# SCH_Wack-a-Mole_2025-09-20.net
KiCad netlist of a schematic drawn in EasyEDA
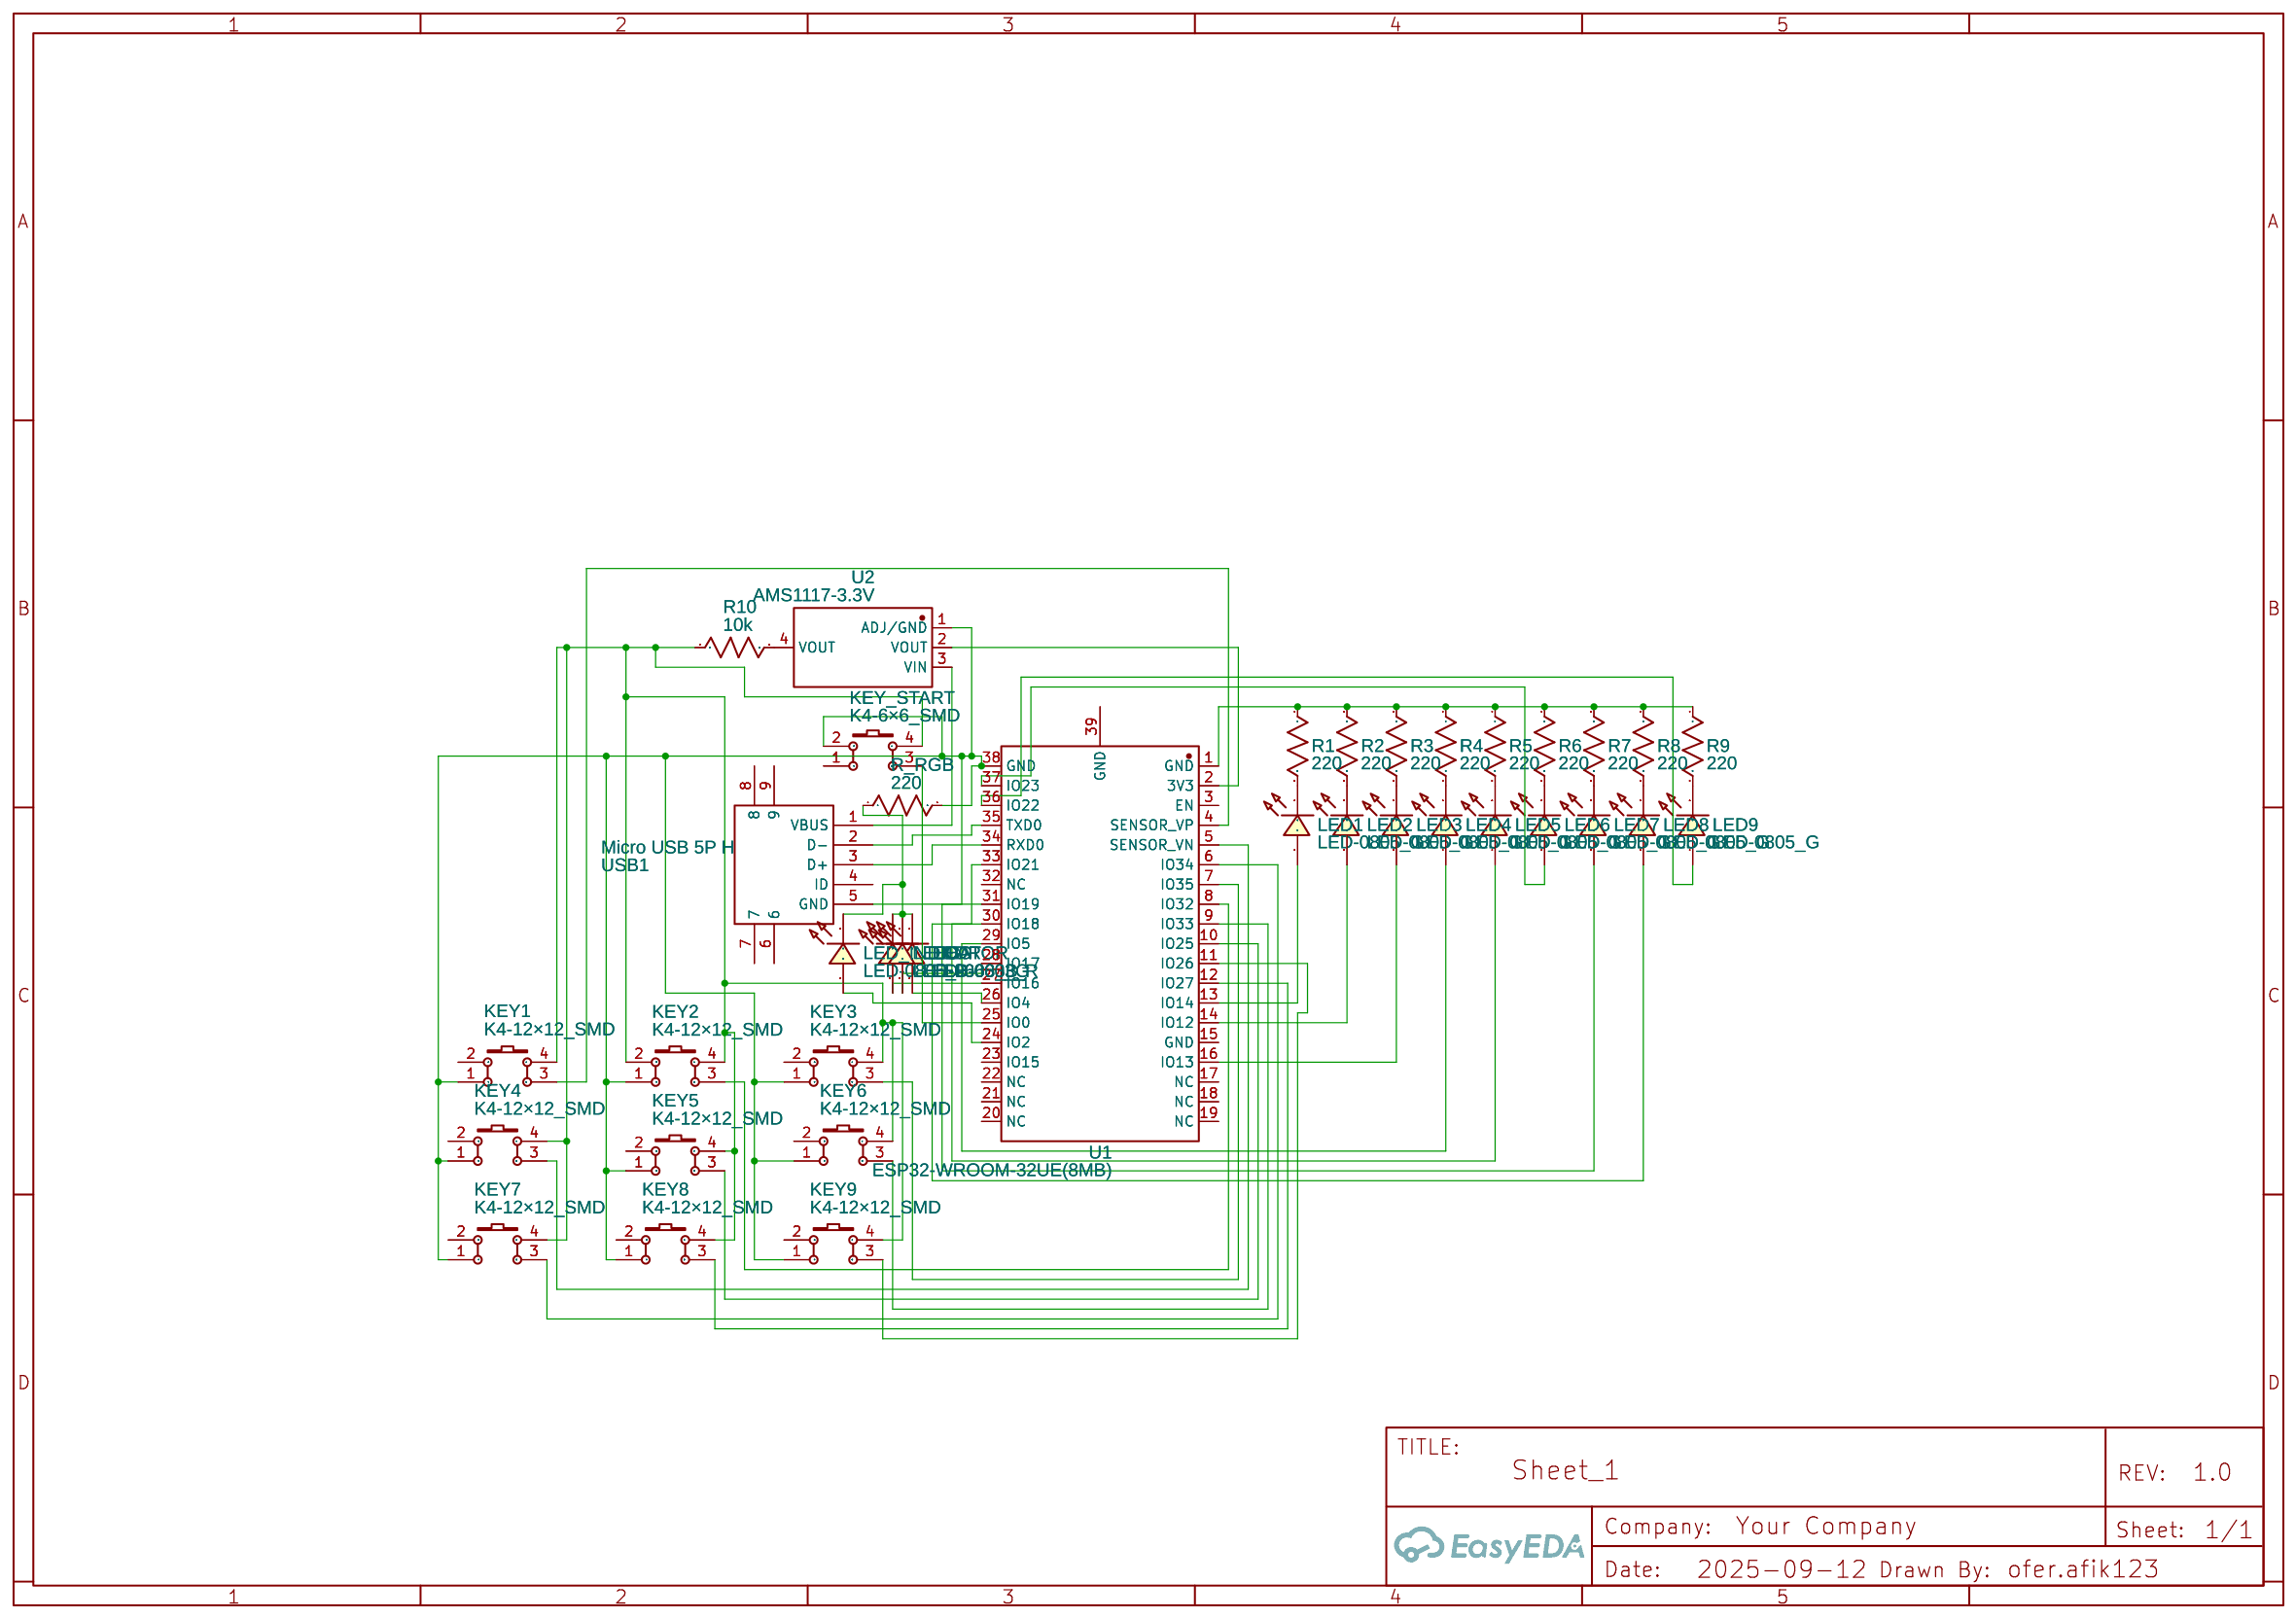
[diagram p0: schematic sheet]

(export (version "E")
  (design (tool "Eeschema 10.0.6"))
  (components
    (comp (ref "KEY1")
      (value "K4-12×12_SMD")
      (fields (field (name "Manufacturer Part") "K2-1103SP-E4SW-04") (field (name "Manufacturer") "韩国韩荣"))
      (libsource (lib "") (part "K4-12×12_SMD"))
    )
    (comp (ref "KEY2")
      (value "K4-12×12_SMD")
      (fields (field (name "Manufacturer Part") "K2-1103SP-E4SW-04") (field (name "Manufacturer") "韩国韩荣"))
      (libsource (lib "") (part "K4-12×12_SMD"))
    )
    (comp (ref "KEY3")
      (value "K4-12×12_SMD")
      (fields (field (name "Manufacturer Part") "K2-1103SP-E4SW-04") (field (name "Manufacturer") "韩国韩荣"))
      (libsource (lib "") (part "K4-12×12_SMD"))
    )
    (comp (ref "KEY4")
      (value "K4-12×12_SMD")
      (fields (field (name "Manufacturer Part") "K2-1103SP-E4SW-04") (field (name "Manufacturer") "韩国韩荣"))
      (libsource (lib "") (part "K4-12×12_SMD"))
    )
    (comp (ref "KEY5")
      (value "K4-12×12_SMD")
      (fields (field (name "Manufacturer Part") "K2-1103SP-E4SW-04") (field (name "Manufacturer") "韩国韩荣"))
      (libsource (lib "") (part "K4-12×12_SMD"))
    )
    (comp (ref "KEY6")
      (value "K4-12×12_SMD")
      (fields (field (name "Manufacturer Part") "K2-1103SP-E4SW-04") (field (name "Manufacturer") "韩国韩荣"))
      (libsource (lib "") (part "K4-12×12_SMD"))
    )
    (comp (ref "KEY7")
      (value "K4-12×12_SMD")
      (fields (field (name "Manufacturer Part") "K2-1103SP-E4SW-04") (field (name "Manufacturer") "韩国韩荣"))
      (libsource (lib "") (part "K4-12×12_SMD"))
    )
    (comp (ref "KEY8")
      (value "K4-12×12_SMD")
      (fields (field (name "Manufacturer Part") "K2-1103SP-E4SW-04") (field (name "Manufacturer") "韩国韩荣"))
      (libsource (lib "") (part "K4-12×12_SMD"))
    )
    (comp (ref "KEY9")
      (value "K4-12×12_SMD")
      (fields (field (name "Manufacturer Part") "K2-1103SP-E4SW-04") (field (name "Manufacturer") "韩国韩荣"))
      (libsource (lib "") (part "K4-12×12_SMD"))
    )
    (comp (ref "KEY_START")
      (value "K4-6×6_SMD")
      (fields (field (name "Manufacturer Part") "K2-6639SP-D4SC-04") (field (name "Manufacturer") "韩国韩荣"))
      (libsource (lib "") (part "K4-6×6_SMD"))
    )
    (comp (ref "LED1")
      (value "LED-0805_G")
      (fields (field (name "Manufacturer Part") "NCD0805G1") (field (name "Manufacturer") "国星光电"))
      (libsource (lib "") (part "LED-0805_G"))
    )
    (comp (ref "LED2")
      (value "LED-0805_G")
      (fields (field (name "Manufacturer Part") "NCD0805G1") (field (name "Manufacturer") "国星光电"))
      (libsource (lib "") (part "LED-0805_G"))
    )
    (comp (ref "LED3")
      (value "LED-0805_G")
      (fields (field (name "Manufacturer Part") "NCD0805G1") (field (name "Manufacturer") "国星光电"))
      (libsource (lib "") (part "LED-0805_G"))
    )
    (comp (ref "LED4")
      (value "LED-0805_G")
      (fields (field (name "Manufacturer Part") "NCD0805G1") (field (name "Manufacturer") "国星光电"))
      (libsource (lib "") (part "LED-0805_G"))
    )
    (comp (ref "LED5")
      (value "LED-0805_G")
      (fields (field (name "Manufacturer Part") "NCD0805G1") (field (name "Manufacturer") "国星光电"))
      (libsource (lib "") (part "LED-0805_G"))
    )
    (comp (ref "LED6")
      (value "LED-0805_G")
      (fields (field (name "Manufacturer Part") "NCD0805G1") (field (name "Manufacturer") "国星光电"))
      (libsource (lib "") (part "LED-0805_G"))
    )
    (comp (ref "LED7")
      (value "LED-0805_G")
      (fields (field (name "Manufacturer Part") "NCD0805G1") (field (name "Manufacturer") "国星光电"))
      (libsource (lib "") (part "LED-0805_G"))
    )
    (comp (ref "LED8")
      (value "LED-0805_G")
      (fields (field (name "Manufacturer Part") "NCD0805G1") (field (name "Manufacturer") "国星光电"))
      (libsource (lib "") (part "LED-0805_G"))
    )
    (comp (ref "LED9")
      (value "LED-0805_G")
      (fields (field (name "Manufacturer Part") "NCD0805G1") (field (name "Manufacturer") "国星光电"))
      (libsource (lib "") (part "LED-0805_G"))
    )
    (comp (ref "LEDB")
      (value "LED-0603_B")
      (fields
        (field (name "Manufacturer Part") "19-217/BHC-ZL1M2RY/3T")
        (field (name "Manufacturer") "EVERLIGHT(台湾亿光)")
      )
      (libsource (lib "") (part "LED-0603_B"))
    )
    (comp (ref "LEDG")
      (value "LED-0603_G")
      (fields
        (field (name "Manufacturer Part") "19-217/GHC-YR1S2/3T")
        (field (name "Manufacturer") "EVERLIGHT(台湾亿光)")
      )
      (libsource (lib "") (part "LED-0603_G"))
    )
    (comp (ref "LEDR")
      (value "LED-0603_R")
      (fields
        (field (name "Manufacturer Part") "19-217/R6C-AL1M2VY/3T")
        (field (name "Manufacturer") "EVERLIGHT(台湾亿光)")
      )
      (libsource (lib "") (part "LED-0603_R"))
    )
    (comp (ref "LED_INDICATOR")
      (value "LED-0805_B")
      (fields (field (name "Manufacturer Part") "D-B080508B1-KS2") (field (name "Manufacturer") "方舟 ARKLED"))
      (libsource (lib "") (part "LED-0805_B"))
    )
    (comp (ref "R1") (value "220") (libsource (lib "") (part "R_0402_US")))
    (comp (ref "R2") (value "220") (libsource (lib "") (part "R_0402_US")))
    (comp (ref "R3") (value "220") (libsource (lib "") (part "R_0402_US")))
    (comp (ref "R4") (value "220") (libsource (lib "") (part "R_0402_US")))
    (comp (ref "R5") (value "220") (libsource (lib "") (part "R_0402_US")))
    (comp (ref "R6") (value "220") (libsource (lib "") (part "R_0402_US")))
    (comp (ref "R7") (value "220") (libsource (lib "") (part "R_0402_US")))
    (comp (ref "R8") (value "220") (libsource (lib "") (part "R_0402_US")))
    (comp (ref "R9") (value "220") (libsource (lib "") (part "R_0402_US")))
    (comp (ref "R10") (value "10k") (libsource (lib "") (part "R_0402_US_1")))
    (comp (ref "R_RGB") (value "220") (libsource (lib "") (part "R_0201_US")))
    (comp (ref "U1")
      (value "ESP32-WROOM-32UE(8MB)")
      (fields
        (field (name "Manufacturer Part") "ESP32-WROOM-32UE-N8")
        (field (name "Manufacturer") "ESPRESSIF(乐鑫)")
      )
      (libsource (lib "") (part "ESP32-WROOM-32UE(8MB)"))
    )
    (comp (ref "U2")
      (value "AMS1117-3.3V")
      (fields (field (name "Manufacturer") "WPMtek(维攀)"))
      (libsource (lib "") (part "AMS1117-3.3V"))
    )
    (comp (ref "USB1")
      (value "Micro USB 5P H")
      (fields (field (name "Manufacturer Part") "920-E52A2021S10101") (field (name "Manufacturer") "精拓金"))
      (libsource (lib "") (part "Micro USB 5P H"))
    )
  )
  (nets
    (net (code "1") (name "Net-(KEY1-Pad4)") (class "Default")
      (node (ref "KEY1") (pin "4") (pinfunction "4_4") (pintype "unspecified"))
      (node (ref "KEY2") (pin "2") (pinfunction "2_2") (pintype "unspecified"))
      (node (ref "KEY2") (pin "4") (pinfunction "4_4") (pintype "unspecified"))
      (node (ref "KEY3") (pin "4") (pinfunction "4_4") (pintype "unspecified"))
      (node (ref "KEY4") (pin "4") (pinfunction "4_4") (pintype "unspecified"))
      (node (ref "KEY5") (pin "4") (pinfunction "4_4") (pintype "unspecified"))
      (node (ref "KEY6") (pin "4") (pinfunction "4_4") (pintype "unspecified"))
      (node (ref "KEY7") (pin "4") (pinfunction "4_4") (pintype "unspecified"))
      (node (ref "KEY8") (pin "4") (pinfunction "4_4") (pintype "unspecified"))
      (node (ref "KEY9") (pin "4") (pinfunction "4_4") (pintype "unspecified"))
      (node (ref "KEY_START") (pin "4") (pinfunction "4_4") (pintype "unspecified"))
      (node (ref "R10") (pin "1") (pinfunction "1_1") (pintype "unspecified"))
    )
    (net (code "2") (name "Net-(LED1-Pad2)") (class "Default")
      (node (ref "LED1") (pin "2") (pinfunction "2_2") (pintype "unspecified"))
      (node (ref "R1") (pin "2") (pinfunction "2_2") (pintype "unspecified"))
    )
    (net (code "3") (name "Net-(LED2-Pad2)") (class "Default")
      (node (ref "LED2") (pin "2") (pinfunction "2_2") (pintype "unspecified"))
      (node (ref "R2") (pin "2") (pinfunction "2_2") (pintype "unspecified"))
    )
    (net (code "4") (name "Net-(LED3-Pad2)") (class "Default")
      (node (ref "LED3") (pin "2") (pinfunction "2_2") (pintype "unspecified"))
      (node (ref "R3") (pin "2") (pinfunction "2_2") (pintype "unspecified"))
    )
    (net (code "5") (name "Net-(LED4-Pad2)") (class "Default")
      (node (ref "LED4") (pin "2") (pinfunction "2_2") (pintype "unspecified"))
      (node (ref "R4") (pin "2") (pinfunction "2_2") (pintype "unspecified"))
    )
    (net (code "6") (name "Net-(LED5-Pad2)") (class "Default")
      (node (ref "LED5") (pin "2") (pinfunction "2_2") (pintype "unspecified"))
      (node (ref "R5") (pin "2") (pinfunction "2_2") (pintype "unspecified"))
    )
    (net (code "7") (name "Net-(LED6-Pad2)") (class "Default")
      (node (ref "LED6") (pin "2") (pinfunction "2_2") (pintype "unspecified"))
      (node (ref "R6") (pin "2") (pinfunction "2_2") (pintype "unspecified"))
    )
    (net (code "8") (name "Net-(LED7-Pad2)") (class "Default")
      (node (ref "LED7") (pin "2") (pinfunction "2_2") (pintype "unspecified"))
      (node (ref "R7") (pin "2") (pinfunction "2_2") (pintype "unspecified"))
    )
    (net (code "9") (name "Net-(LED8-Pad2)") (class "Default")
      (node (ref "LED8") (pin "2") (pinfunction "2_2") (pintype "unspecified"))
      (node (ref "R8") (pin "2") (pinfunction "2_2") (pintype "unspecified"))
    )
    (net (code "10") (name "Net-(LED9-Pad2)") (class "Default")
      (node (ref "LED9") (pin "2") (pinfunction "2_2") (pintype "unspecified"))
      (node (ref "R9") (pin "2") (pinfunction "2_2") (pintype "unspecified"))
    )
    (net (code "11") (name "Net-(LEDB-Pad2)") (class "Default")
      (node (ref "LEDB") (pin "2") (pinfunction "2_2") (pintype "unspecified"))
      (node (ref "LEDG") (pin "2") (pinfunction "2_2") (pintype "unspecified"))
      (node (ref "LEDR") (pin "2") (pinfunction "2_2") (pintype "unspecified"))
      (node (ref "LED_INDICATOR") (pin "2") (pinfunction "2_2") (pintype "unspecified"))
      (node (ref "R_RGB") (pin "1") (pinfunction "1_1") (pintype "unspecified"))
    )
    (net (code "12") (name "Net-(R1-Pad1)") (class "Default")
      (node (ref "R1") (pin "1") (pinfunction "1_1") (pintype "unspecified"))
      (node (ref "R2") (pin "1") (pinfunction "1_1") (pintype "unspecified"))
      (node (ref "R3") (pin "1") (pinfunction "1_1") (pintype "unspecified"))
      (node (ref "R4") (pin "1") (pinfunction "1_1") (pintype "unspecified"))
      (node (ref "R5") (pin "1") (pinfunction "1_1") (pintype "unspecified"))
      (node (ref "R6") (pin "1") (pinfunction "1_1") (pintype "unspecified"))
      (node (ref "R7") (pin "1") (pinfunction "1_1") (pintype "unspecified"))
      (node (ref "R8") (pin "1") (pinfunction "1_1") (pintype "unspecified"))
      (node (ref "R9") (pin "1") (pinfunction "1_1") (pintype "unspecified"))
      (node (ref "U1") (pin "1") (pinfunction "GND_1") (pintype "unspecified"))
    )
    (net (code "13") (name "Net-(R10-Pad2)") (class "Default")
      (node (ref "R10") (pin "2") (pinfunction "2_2") (pintype "unspecified"))
      (node (ref "U2") (pin "4") (pinfunction "VOUT_4") (pintype "unspecified"))
    )
    (net (code "14") (name "Net-(U1-3V3)") (class "Default")
      (node (ref "U1") (pin "2") (pinfunction "3V3_2") (pintype "unspecified"))
      (node (ref "U2") (pin "2") (pinfunction "VOUT_2") (pintype "unspecified"))
    )
    (net (code "15") (name "Net-(U1-IO0)") (class "Default")
      (node (ref "KEY_START") (pin "3") (pinfunction "3_3") (pintype "unspecified"))
      (node (ref "U1") (pin "25") (pinfunction "IO0_25") (pintype "unspecified"))
    )
    (net (code "16") (name "Net-(U1-IO2)") (class "Default")
      (node (ref "LED_INDICATOR") (pin "1") (pinfunction "1_1") (pintype "unspecified"))
      (node (ref "U1") (pin "24") (pinfunction "IO2_24") (pintype "unspecified"))
    )
    (net (code "17") (name "Net-(U1-IO4)") (class "Default")
      (node (ref "LEDR") (pin "1") (pinfunction "1_1") (pintype "unspecified"))
      (node (ref "U1") (pin "26") (pinfunction "IO4_26") (pintype "unspecified"))
    )
    (net (code "18") (name "Net-(U1-IO5)") (class "Default")
      (node (ref "LED4") (pin "1") (pinfunction "1_1") (pintype "unspecified"))
      (node (ref "U1") (pin "29") (pinfunction "IO5_29") (pintype "unspecified"))
    )
    (net (code "19") (name "Net-(U1-IO12)") (class "Default")
      (node (ref "LED2") (pin "1") (pinfunction "1_1") (pintype "unspecified"))
      (node (ref "U1") (pin "14") (pinfunction "IO12_14") (pintype "unspecified"))
    )
    (net (code "20") (name "Net-(U1-IO13)") (class "Default")
      (node (ref "LED3") (pin "1") (pinfunction "1_1") (pintype "unspecified"))
      (node (ref "U1") (pin "16") (pinfunction "IO13_16") (pintype "unspecified"))
    )
    (net (code "21") (name "Net-(U1-IO14)") (class "Default")
      (node (ref "LED1") (pin "1") (pinfunction "1_1") (pintype "unspecified"))
      (node (ref "U1") (pin "13") (pinfunction "IO14_13") (pintype "unspecified"))
    )
    (net (code "22") (name "Net-(U1-IO16)") (class "Default")
      (node (ref "LEDB") (pin "1") (pinfunction "1_1") (pintype "unspecified"))
      (node (ref "U1") (pin "27") (pinfunction "IO16_27") (pintype "unspecified"))
    )
    (net (code "23") (name "Net-(U1-IO17)") (class "Default")
      (node (ref "LEDG") (pin "1") (pinfunction "1_1") (pintype "unspecified"))
      (node (ref "U1") (pin "28") (pinfunction "IO17_28") (pintype "unspecified"))
    )
    (net (code "24") (name "Net-(U1-IO18)") (class "Default")
      (node (ref "LED8") (pin "1") (pinfunction "1_1") (pintype "unspecified"))
      (node (ref "U1") (pin "30") (pinfunction "IO18_30") (pintype "unspecified"))
    )
    (net (code "25") (name "Net-(U1-IO19)") (class "Default")
      (node (ref "LED7") (pin "1") (pinfunction "1_1") (pintype "unspecified"))
      (node (ref "U1") (pin "31") (pinfunction "IO19_31") (pintype "unspecified"))
    )
    (net (code "26") (name "Net-(U1-IO21)") (class "Default")
      (node (ref "LED5") (pin "1") (pinfunction "1_1") (pintype "unspecified"))
      (node (ref "U1") (pin "33") (pinfunction "IO21_33") (pintype "unspecified"))
    )
    (net (code "27") (name "Net-(U1-IO22)") (class "Default")
      (node (ref "LED9") (pin "1") (pinfunction "1_1") (pintype "unspecified"))
      (node (ref "U1") (pin "36") (pinfunction "IO22_36") (pintype "unspecified"))
    )
    (net (code "28") (name "Net-(U1-IO23)") (class "Default")
      (node (ref "LED6") (pin "1") (pinfunction "1_1") (pintype "unspecified"))
      (node (ref "U1") (pin "37") (pinfunction "IO23_37") (pintype "unspecified"))
    )
    (net (code "29") (name "Net-(U1-IO25)") (class "Default")
      (node (ref "KEY5") (pin "3") (pinfunction "3_3") (pintype "unspecified"))
      (node (ref "U1") (pin "10") (pinfunction "IO25_10") (pintype "unspecified"))
    )
    (net (code "30") (name "Net-(U1-IO26)") (class "Default")
      (node (ref "KEY9") (pin "3") (pinfunction "3_3") (pintype "unspecified"))
      (node (ref "U1") (pin "11") (pinfunction "IO26_11") (pintype "unspecified"))
    )
    (net (code "31") (name "Net-(U1-IO27)") (class "Default")
      (node (ref "KEY8") (pin "3") (pinfunction "3_3") (pintype "unspecified"))
      (node (ref "U1") (pin "12") (pinfunction "IO27_12") (pintype "unspecified"))
    )
    (net (code "32") (name "Net-(U1-IO32)") (class "Default")
      (node (ref "KEY2") (pin "3") (pinfunction "3_3") (pintype "unspecified"))
      (node (ref "U1") (pin "8") (pinfunction "IO32_8") (pintype "unspecified"))
    )
    (net (code "33") (name "Net-(U1-IO33)") (class "Default")
      (node (ref "KEY6") (pin "3") (pinfunction "3_3") (pintype "unspecified"))
      (node (ref "U1") (pin "9") (pinfunction "IO33_9") (pintype "unspecified"))
    )
    (net (code "34") (name "Net-(U1-IO34)") (class "Default")
      (node (ref "KEY7") (pin "3") (pinfunction "3_3") (pintype "unspecified"))
      (node (ref "U1") (pin "6") (pinfunction "IO34_6") (pintype "unspecified"))
    )
    (net (code "35") (name "Net-(U1-IO35)") (class "Default")
      (node (ref "KEY3") (pin "3") (pinfunction "3_3") (pintype "unspecified"))
      (node (ref "U1") (pin "7") (pinfunction "IO35_7") (pintype "unspecified"))
    )
    (net (code "36") (name "Net-(U1-RXD0)") (class "Default")
      (node (ref "U1") (pin "34") (pinfunction "RXD0_34") (pintype "unspecified"))
      (node (ref "USB1") (pin "3") (pinfunction "D+_3") (pintype "unspecified"))
    )
    (net (code "37") (name "Net-(U1-SENSOR_VN)") (class "Default")
      (node (ref "KEY4") (pin "3") (pinfunction "3_3") (pintype "unspecified"))
      (node (ref "U1") (pin "5") (pinfunction "SENSOR_VN_5") (pintype "unspecified"))
    )
    (net (code "38") (name "Net-(U1-SENSOR_VP)") (class "Default")
      (node (ref "KEY1") (pin "3") (pinfunction "3_3") (pintype "unspecified"))
      (node (ref "U1") (pin "4") (pinfunction "SENSOR_VP_4") (pintype "unspecified"))
    )
    (net (code "39") (name "Net-(U1-TXD0)") (class "Default")
      (node (ref "U1") (pin "35") (pinfunction "TXD0_35") (pintype "unspecified"))
      (node (ref "USB1") (pin "2") (pinfunction "D-_2") (pintype "unspecified"))
    )
    (net (code "40") (name "Net-(U2-ADJ{slash}GND)") (class "Default")
      (node (ref "KEY1") (pin "1") (pinfunction "1_1") (pintype "unspecified"))
      (node (ref "KEY2") (pin "1") (pinfunction "1_1") (pintype "unspecified"))
      (node (ref "KEY3") (pin "1") (pinfunction "1_1") (pintype "unspecified"))
      (node (ref "KEY4") (pin "1") (pinfunction "1_1") (pintype "unspecified"))
      (node (ref "KEY5") (pin "1") (pinfunction "1_1") (pintype "unspecified"))
      (node (ref "KEY6") (pin "1") (pinfunction "1_1") (pintype "unspecified"))
      (node (ref "KEY7") (pin "1") (pinfunction "1_1") (pintype "unspecified"))
      (node (ref "KEY8") (pin "1") (pinfunction "1_1") (pintype "unspecified"))
      (node (ref "KEY9") (pin "1") (pinfunction "1_1") (pintype "unspecified"))
      (node (ref "KEY_START") (pin "2") (pinfunction "2_2") (pintype "unspecified"))
      (node (ref "R_RGB") (pin "2") (pinfunction "2_2") (pintype "unspecified"))
      (node (ref "U1") (pin "38") (pinfunction "GND_38") (pintype "unspecified"))
      (node (ref "U2") (pin "1") (pinfunction "ADJ/GND_1") (pintype "unspecified"))
      (node (ref "USB1") (pin "5") (pinfunction "GND_5") (pintype "unspecified"))
    )
    (net (code "41") (name "Net-(U2-VIN)") (class "Default")
      (node (ref "U2") (pin "3") (pinfunction "VIN_3") (pintype "unspecified"))
      (node (ref "USB1") (pin "1") (pinfunction "VBUS_1") (pintype "unspecified"))
    )
    (net (code "42") (name "unconnected-(KEY1-Pad2)") (class "Default")
      (node (ref "KEY1") (pin "2") (pinfunction "2_2") (pintype "unspecified"))
    )
    (net (code "43") (name "unconnected-(KEY3-Pad2)") (class "Default")
      (node (ref "KEY3") (pin "2") (pinfunction "2_2") (pintype "unspecified"))
    )
    (net (code "44") (name "unconnected-(KEY4-Pad2)") (class "Default")
      (node (ref "KEY4") (pin "2") (pinfunction "2_2") (pintype "unspecified"))
    )
    (net (code "45") (name "unconnected-(KEY5-Pad2)") (class "Default")
      (node (ref "KEY5") (pin "2") (pinfunction "2_2") (pintype "unspecified"))
    )
    (net (code "46") (name "unconnected-(KEY6-Pad2)") (class "Default")
      (node (ref "KEY6") (pin "2") (pinfunction "2_2") (pintype "unspecified"))
    )
    (net (code "47") (name "unconnected-(KEY7-Pad2)") (class "Default")
      (node (ref "KEY7") (pin "2") (pinfunction "2_2") (pintype "unspecified"))
    )
    (net (code "48") (name "unconnected-(KEY8-Pad2)") (class "Default")
      (node (ref "KEY8") (pin "2") (pinfunction "2_2") (pintype "unspecified"))
    )
    (net (code "49") (name "unconnected-(KEY9-Pad2)") (class "Default")
      (node (ref "KEY9") (pin "2") (pinfunction "2_2") (pintype "unspecified"))
    )
    (net (code "50") (name "unconnected-(KEY_START-Pad1)") (class "Default")
      (node (ref "KEY_START") (pin "1") (pinfunction "1_1") (pintype "unspecified"))
    )
    (net (code "51") (name "unconnected-(U1-EN-Pad3)") (class "Default")
      (node (ref "U1") (pin "3") (pinfunction "EN_3") (pintype "unspecified"))
    )
    (net (code "52") (name "unconnected-(U1-GND-Pad15)") (class "Default")
      (node (ref "U1") (pin "15") (pinfunction "GND_15") (pintype "unspecified"))
    )
    (net (code "53") (name "unconnected-(U1-GND-Pad39)") (class "Default")
      (node (ref "U1") (pin "39") (pinfunction "GND_39") (pintype "unspecified"))
    )
    (net (code "54") (name "unconnected-(U1-IO15-Pad23)") (class "Default")
      (node (ref "U1") (pin "23") (pinfunction "IO15_23") (pintype "unspecified"))
    )
    (net (code "55") (name "unconnected-(U1-NC-Pad17)") (class "Default")
      (node (ref "U1") (pin "17") (pinfunction "NC_17") (pintype "unspecified"))
    )
    (net (code "56") (name "unconnected-(U1-NC-Pad18)") (class "Default")
      (node (ref "U1") (pin "18") (pinfunction "NC_18") (pintype "unspecified"))
    )
    (net (code "57") (name "unconnected-(U1-NC-Pad19)") (class "Default")
      (node (ref "U1") (pin "19") (pinfunction "NC_19") (pintype "unspecified"))
    )
    (net (code "58") (name "unconnected-(U1-NC-Pad20)") (class "Default")
      (node (ref "U1") (pin "20") (pinfunction "NC_20") (pintype "unspecified"))
    )
    (net (code "59") (name "unconnected-(U1-NC-Pad21)") (class "Default")
      (node (ref "U1") (pin "21") (pinfunction "NC_21") (pintype "unspecified"))
    )
    (net (code "60") (name "unconnected-(U1-NC-Pad22)") (class "Default")
      (node (ref "U1") (pin "22") (pinfunction "NC_22") (pintype "unspecified"))
    )
    (net (code "61") (name "unconnected-(U1-NC-Pad32)") (class "Default")
      (node (ref "U1") (pin "32") (pinfunction "NC_32") (pintype "unspecified"))
    )
    (net (code "62") (name "unconnected-(USB1-ID-Pad4)") (class "Default")
      (node (ref "USB1") (pin "4") (pinfunction "ID_4") (pintype "unspecified"))
    )
    (net (code "63") (name "unconnected-(USB1-Pad6)") (class "Default")
      (node (ref "USB1") (pin "6") (pinfunction "6_6") (pintype "unspecified"))
    )
    (net (code "64") (name "unconnected-(USB1-Pad7)") (class "Default")
      (node (ref "USB1") (pin "7") (pinfunction "7_7") (pintype "unspecified"))
    )
    (net (code "65") (name "unconnected-(USB1-Pad8)") (class "Default")
      (node (ref "USB1") (pin "8") (pinfunction "8_8") (pintype "unspecified"))
    )
    (net (code "66") (name "unconnected-(USB1-Pad9)") (class "Default")
      (node (ref "USB1") (pin "9") (pinfunction "9_9") (pintype "unspecified"))
    )
  )
)
